# 13_-_ETHERNET_PHY.net
KiCad netlist of a schematic drawn in Altium Designer
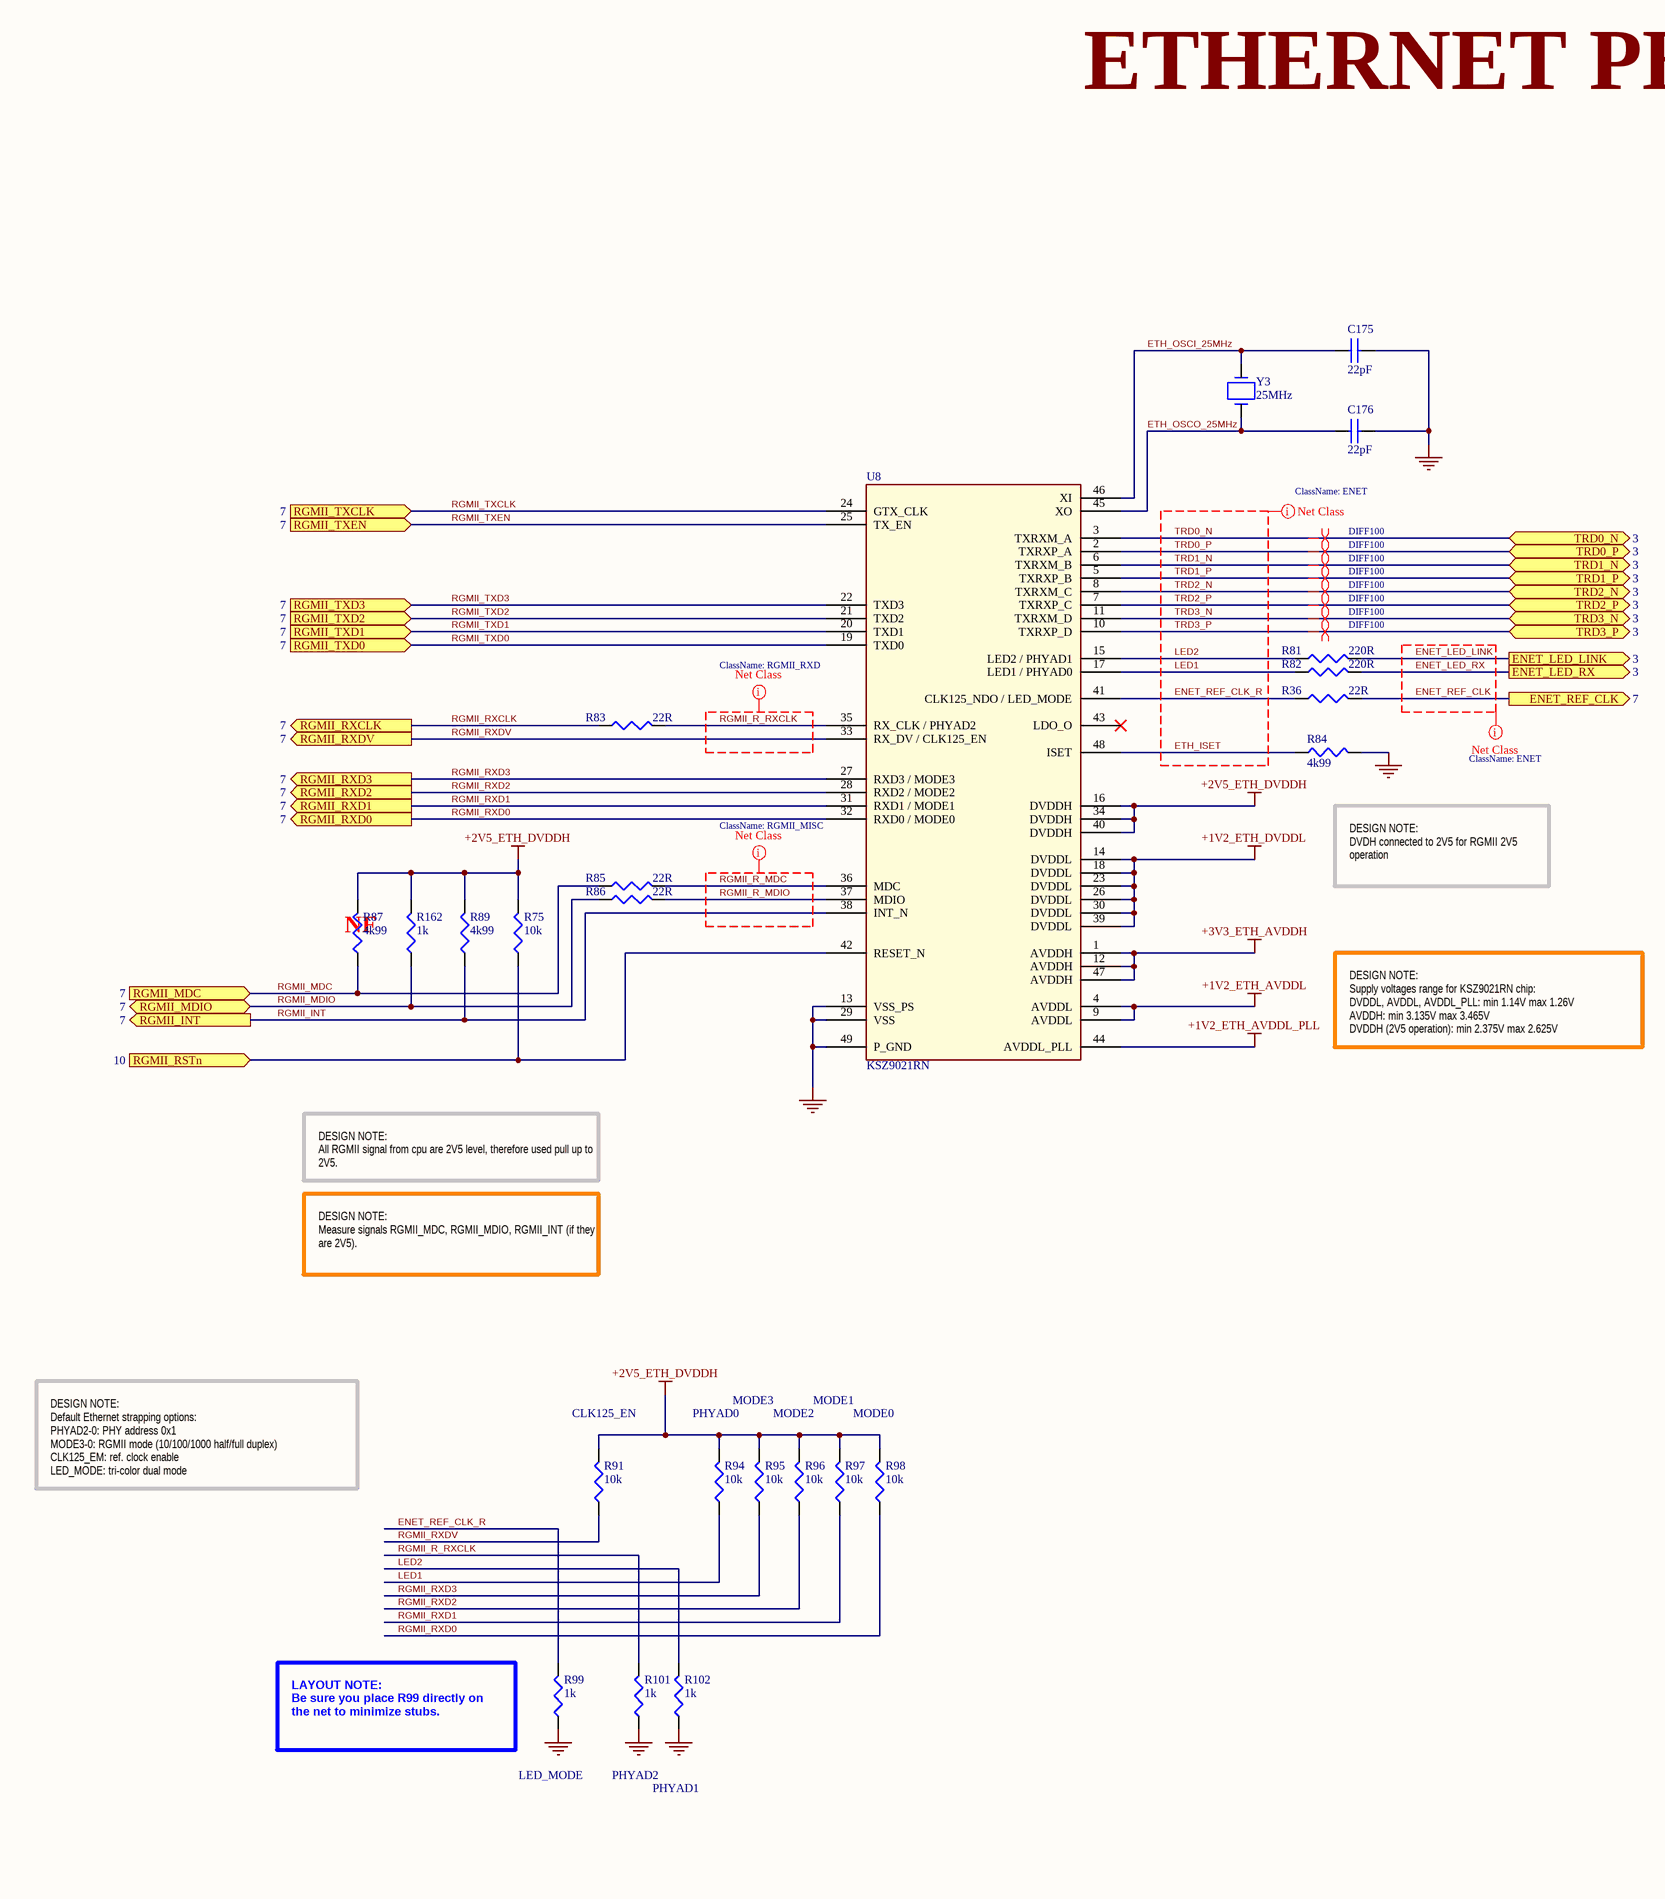
[diagram p0: [13] - ETHERNET PHY.SchDoc, left]
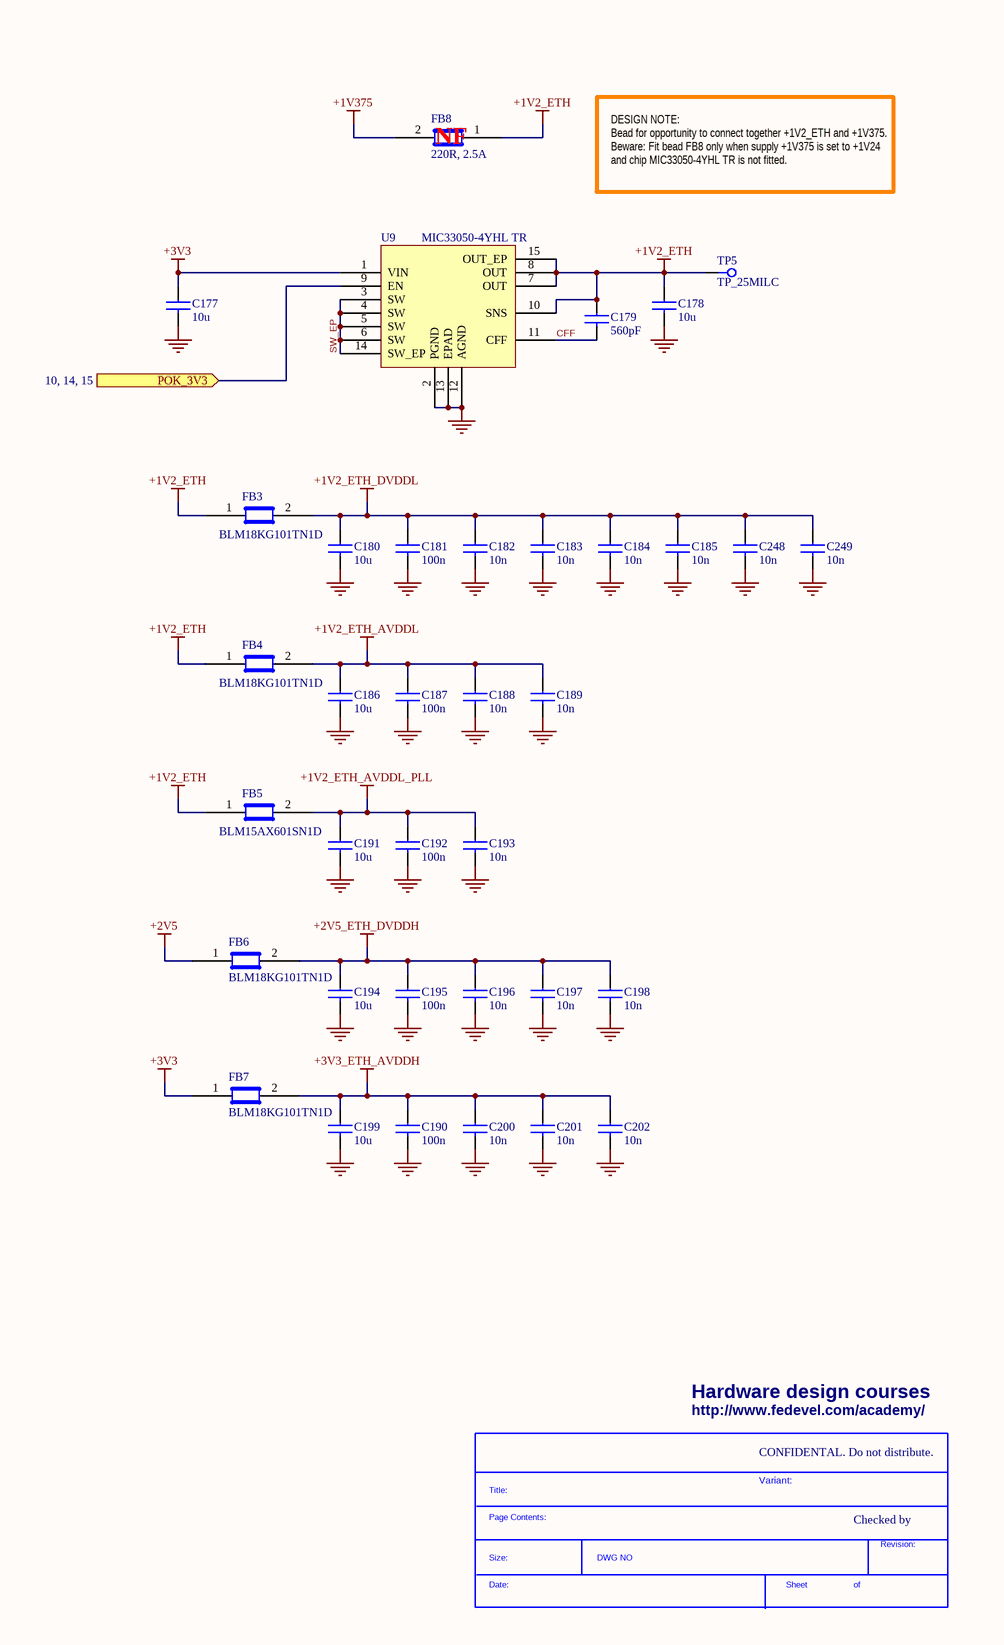
[diagram p1: [13] - ETHERNET PHY.SchDoc, right]

(export (version "E")
  (design (tool "Eeschema 10.0.6"))
  (components
    (comp (ref "C175")
      (value "22pF")
      (footprint "C0402")
      (description "CAP CER 22PF 50V C0G 5% 0402")
      (fields
        (field (name "MANUFACTURER") "TDK Corporation")
        (field (name "MANUFACTURER PART NUMBER") "C1005C0G1H220J")
      )
      (libsource (lib "Integrated_Library_RF_FEB_2012") (part "C1005C0G1H220J"))
    )
    (comp (ref "C176")
      (value "22pF")
      (footprint "C0402")
      (description "CAP CER 22PF 50V C0G 5% 0402")
      (fields
        (field (name "MANUFACTURER") "TDK Corporation")
        (field (name "MANUFACTURER PART NUMBER") "C1005C0G1H220J")
      )
      (libsource (lib "Integrated_Library_RF_FEB_2012") (part "C1005C0G1H220J"))
    )
    (comp (ref "C177")
      (value "10u")
      (footprint "C0603")
      (description "CAP CER 10UF 6.3V X5R 20% 0603")
      (fields
        (field (name "MANUFACTURER") "TDK Corporation")
        (field (name "MANUFACTURER PART NUMBER") "C1608X5R0J106M")
      )
      (libsource (lib "Integrated_Library_RF_FEB_2012") (part "C1608X5R0J106M"))
    )
    (comp (ref "C178")
      (value "10u")
      (footprint "C0603")
      (description "CAP CER 10UF 6.3V X5R 20% 0603")
      (fields
        (field (name "MANUFACTURER") "TDK Corporation")
        (field (name "MANUFACTURER PART NUMBER") "C1608X5R0J106M")
      )
      (libsource (lib "Integrated_Library_RF_FEB_2012") (part "C1608X5R0J106M"))
    )
    (comp (ref "C179")
      (value "560pF")
      (footprint "C0402")
      (description "CAP CER 560PF 50V C0G 0402")
      (fields
        (field (name "MANUFACTURER") "Murata Electronics North America")
        (field (name "MANUFACTURER PART NUMBER") "GRM1555C1H561JA01D")
      )
      (libsource (lib "Integrated_Library_RF_FEB_2012") (part "GRM1555C1H561JA01D"))
    )
    (comp (ref "C180")
      (value "10u")
      (footprint "C0603")
      (description "CAP CER 10UF 6.3V X5R 20% 0603")
      (fields
        (field (name "MANUFACTURER") "TDK Corporation")
        (field (name "MANUFACTURER PART NUMBER") "C1608X5R0J106M")
      )
      (libsource (lib "Integrated_Library_RF_FEB_2012") (part "C1608X5R0J106M"))
    )
    (comp (ref "C181")
      (value "100n")
      (footprint "C0402")
      (description "CAP CER .10UF 50V X5R 10% 0402")
      (fields
        (field (name "MANUFACTURER") "TDK Corporation")
        (field (name "MANUFACTURER PART NUMBER") "C1005X5R1H104K")
      )
      (libsource (lib "Integrated_Library_RF_FEB_2012") (part "C1005X5R1H104K"))
    )
    (comp (ref "C182")
      (value "10n")
      (footprint "C0402")
      (description "CAP CER 10000PF 16V X7R 10% 0402")
      (fields
        (field (name "MANUFACTURER") "TDK Corporation")
        (field (name "MANUFACTURER PART NUMBER") "C1005X7R1C103K")
      )
      (libsource (lib "Integrated_Library_RF_FEB_2012") (part "C1005X7R1C103K"))
    )
    (comp (ref "C183")
      (value "10n")
      (footprint "C0402")
      (description "CAP CER 10000PF 16V X7R 10% 0402")
      (fields
        (field (name "MANUFACTURER") "TDK Corporation")
        (field (name "MANUFACTURER PART NUMBER") "C1005X7R1C103K")
      )
      (libsource (lib "Integrated_Library_RF_FEB_2012") (part "C1005X7R1C103K"))
    )
    (comp (ref "C184")
      (value "10n")
      (footprint "C0402")
      (description "CAP CER 10000PF 16V X7R 10% 0402")
      (fields
        (field (name "MANUFACTURER") "TDK Corporation")
        (field (name "MANUFACTURER PART NUMBER") "C1005X7R1C103K")
      )
      (libsource (lib "Integrated_Library_RF_FEB_2012") (part "C1005X7R1C103K"))
    )
    (comp (ref "C185")
      (value "10n")
      (footprint "C0402")
      (description "CAP CER 10000PF 16V X7R 10% 0402")
      (fields
        (field (name "MANUFACTURER") "TDK Corporation")
        (field (name "MANUFACTURER PART NUMBER") "C1005X7R1C103K")
      )
      (libsource (lib "Integrated_Library_RF_FEB_2012") (part "C1005X7R1C103K"))
    )
    (comp (ref "C186")
      (value "10u")
      (footprint "C0603")
      (description "CAP CER 10UF 6.3V X5R 20% 0603")
      (fields
        (field (name "MANUFACTURER") "TDK Corporation")
        (field (name "MANUFACTURER PART NUMBER") "C1608X5R0J106M")
      )
      (libsource (lib "Integrated_Library_RF_FEB_2012") (part "C1608X5R0J106M"))
    )
    (comp (ref "C187")
      (value "100n")
      (footprint "C0402")
      (description "CAP CER .10UF 50V X5R 10% 0402")
      (fields
        (field (name "MANUFACTURER") "TDK Corporation")
        (field (name "MANUFACTURER PART NUMBER") "C1005X5R1H104K")
      )
      (libsource (lib "Integrated_Library_RF_FEB_2012") (part "C1005X5R1H104K"))
    )
    (comp (ref "C188")
      (value "10n")
      (footprint "C0402")
      (description "CAP CER 10000PF 16V X7R 10% 0402")
      (fields
        (field (name "MANUFACTURER") "TDK Corporation")
        (field (name "MANUFACTURER PART NUMBER") "C1005X7R1C103K")
      )
      (libsource (lib "Integrated_Library_RF_FEB_2012") (part "C1005X7R1C103K"))
    )
    (comp (ref "C189")
      (value "10n")
      (footprint "C0402")
      (description "CAP CER 10000PF 16V X7R 10% 0402")
      (fields
        (field (name "MANUFACTURER") "TDK Corporation")
        (field (name "MANUFACTURER PART NUMBER") "C1005X7R1C103K")
      )
      (libsource (lib "Integrated_Library_RF_FEB_2012") (part "C1005X7R1C103K"))
    )
    (comp (ref "C190")
      (value "100n")
      (footprint "C0402")
      (description "CAP CER .10UF 50V X5R 10% 0402")
      (fields
        (field (name "MANUFACTURER") "TDK Corporation")
        (field (name "MANUFACTURER PART NUMBER") "C1005X5R1H104K")
      )
      (libsource (lib "Integrated_Library_RF_FEB_2012") (part "C1005X5R1H104K"))
    )
    (comp (ref "C191")
      (value "10u")
      (footprint "C0603")
      (description "CAP CER 10UF 6.3V X5R 20% 0603")
      (fields
        (field (name "MANUFACTURER") "TDK Corporation")
        (field (name "MANUFACTURER PART NUMBER") "C1608X5R0J106M")
      )
      (libsource (lib "Integrated_Library_RF_FEB_2012") (part "C1608X5R0J106M"))
    )
    (comp (ref "C192")
      (value "100n")
      (footprint "C0402")
      (description "CAP CER .10UF 50V X5R 10% 0402")
      (fields
        (field (name "MANUFACTURER") "TDK Corporation")
        (field (name "MANUFACTURER PART NUMBER") "C1005X5R1H104K")
      )
      (libsource (lib "Integrated_Library_RF_FEB_2012") (part "C1005X5R1H104K"))
    )
    (comp (ref "C193")
      (value "10n")
      (footprint "C0402")
      (description "CAP CER 10000PF 16V X7R 10% 0402")
      (fields
        (field (name "MANUFACTURER") "TDK Corporation")
        (field (name "MANUFACTURER PART NUMBER") "C1005X7R1C103K")
      )
      (libsource (lib "Integrated_Library_RF_FEB_2012") (part "C1005X7R1C103K"))
    )
    (comp (ref "C194")
      (value "10u")
      (footprint "C0603")
      (description "CAP CER 10UF 6.3V X5R 20% 0603")
      (fields
        (field (name "MANUFACTURER") "TDK Corporation")
        (field (name "MANUFACTURER PART NUMBER") "C1608X5R0J106M")
      )
      (libsource (lib "Integrated_Library_RF_FEB_2012") (part "C1608X5R0J106M"))
    )
    (comp (ref "C195")
      (value "100n")
      (footprint "C0402")
      (description "CAP CER .10UF 50V X5R 10% 0402")
      (fields
        (field (name "MANUFACTURER") "TDK Corporation")
        (field (name "MANUFACTURER PART NUMBER") "C1005X5R1H104K")
      )
      (libsource (lib "Integrated_Library_RF_FEB_2012") (part "C1005X5R1H104K"))
    )
    (comp (ref "C196")
      (value "10n")
      (footprint "C0402")
      (description "CAP CER 10000PF 16V X7R 10% 0402")
      (fields
        (field (name "MANUFACTURER") "TDK Corporation")
        (field (name "MANUFACTURER PART NUMBER") "C1005X7R1C103K")
      )
      (libsource (lib "Integrated_Library_RF_FEB_2012") (part "C1005X7R1C103K"))
    )
    (comp (ref "C197")
      (value "10n")
      (footprint "C0402")
      (description "CAP CER 10000PF 16V X7R 10% 0402")
      (fields
        (field (name "MANUFACTURER") "TDK Corporation")
        (field (name "MANUFACTURER PART NUMBER") "C1005X7R1C103K")
      )
      (libsource (lib "Integrated_Library_RF_FEB_2012") (part "C1005X7R1C103K"))
    )
    (comp (ref "C198")
      (value "10n")
      (footprint "C0402")
      (description "CAP CER 10000PF 16V X7R 10% 0402")
      (fields
        (field (name "MANUFACTURER") "TDK Corporation")
        (field (name "MANUFACTURER PART NUMBER") "C1005X7R1C103K")
      )
      (libsource (lib "Integrated_Library_RF_FEB_2012") (part "C1005X7R1C103K"))
    )
    (comp (ref "C199")
      (value "10u")
      (footprint "C0603")
      (description "CAP CER 10UF 6.3V X5R 20% 0603")
      (fields
        (field (name "MANUFACTURER") "TDK Corporation")
        (field (name "MANUFACTURER PART NUMBER") "C1608X5R0J106M")
      )
      (libsource (lib "Integrated_Library_RF_FEB_2012") (part "C1608X5R0J106M"))
    )
    (comp (ref "C200")
      (value "10n")
      (footprint "C0402")
      (description "CAP CER 10000PF 16V X7R 10% 0402")
      (fields
        (field (name "MANUFACTURER") "TDK Corporation")
        (field (name "MANUFACTURER PART NUMBER") "C1005X7R1C103K")
      )
      (libsource (lib "Integrated_Library_RF_FEB_2012") (part "C1005X7R1C103K"))
    )
    (comp (ref "C201")
      (value "10n")
      (footprint "C0402")
      (description "CAP CER 10000PF 16V X7R 10% 0402")
      (fields
        (field (name "MANUFACTURER") "TDK Corporation")
        (field (name "MANUFACTURER PART NUMBER") "C1005X7R1C103K")
      )
      (libsource (lib "Integrated_Library_RF_FEB_2012") (part "C1005X7R1C103K"))
    )
    (comp (ref "C202")
      (value "10n")
      (footprint "C0402")
      (description "CAP CER 10000PF 16V X7R 10% 0402")
      (fields
        (field (name "MANUFACTURER") "TDK Corporation")
        (field (name "MANUFACTURER PART NUMBER") "C1005X7R1C103K")
      )
      (libsource (lib "Integrated_Library_RF_FEB_2012") (part "C1005X7R1C103K"))
    )
    (comp (ref "C248")
      (value "10n")
      (footprint "C0402")
      (description "CAP CER 10000PF 16V X7R 10% 0402")
      (fields
        (field (name "MANUFACTURER") "TDK Corporation")
        (field (name "MANUFACTURER PART NUMBER") "C1005X7R1C103K")
      )
      (libsource (lib "Integrated_Library_RF_FEB_2012") (part "C1005X7R1C103K"))
    )
    (comp (ref "C249")
      (value "10n")
      (footprint "C0402")
      (description "CAP CER 10000PF 16V X7R 10% 0402")
      (fields
        (field (name "MANUFACTURER") "TDK Corporation")
        (field (name "MANUFACTURER PART NUMBER") "C1005X7R1C103K")
      )
      (libsource (lib "Integrated_Library_RF_FEB_2012") (part "C1005X7R1C103K"))
    )
    (comp (ref "FB3")
      (value "BLM18KG101TN1D")
      (footprint "C0603")
      (description "FERRITE CHIP 100 OHM BEAD 0603")
      (fields (field (name "MANUFACTURER") "Murata Electronics North America"))
      (libsource (lib "Integrated_Library_RF_FEB_2012") (part "BLM18KG101TN1D"))
    )
    (comp (ref "FB4")
      (value "BLM18KG101TN1D")
      (footprint "C0603")
      (description "FERRITE CHIP 100 OHM BEAD 0603")
      (fields (field (name "MANUFACTURER") "Murata Electronics North America"))
      (libsource (lib "Integrated_Library_RF_FEB_2012") (part "BLM18KG101TN1D"))
    )
    (comp (ref "FB5")
      (value "BLM15AX601SN1D")
      (footprint "C0402")
      (description "FERRITE CHIP 600 OHM 0402")
      (fields (field (name "MANUFACTURER") "Murata Electronics North America"))
      (libsource (lib "Integrated_Library_RF_FEB_2012") (part "BLM15AX601SN1D"))
    )
    (comp (ref "FB6")
      (value "BLM18KG101TN1D")
      (footprint "C0603")
      (description "FERRITE CHIP 100 OHM BEAD 0603")
      (fields (field (name "MANUFACTURER") "Murata Electronics North America"))
      (libsource (lib "Integrated_Library_RF_FEB_2012") (part "BLM18KG101TN1D"))
    )
    (comp (ref "FB7")
      (value "BLM18KG101TN1D")
      (footprint "C0603")
      (description "FERRITE CHIP 100 OHM BEAD 0603")
      (fields (field (name "MANUFACTURER") "Murata Electronics North America"))
      (libsource (lib "Integrated_Library_RF_FEB_2012") (part "BLM18KG101TN1D"))
    )
    (comp (ref "FB8")
      (value "220R, 2.5A")
      (footprint "C0603")
      (description "FERRITE CHIP 220 OHM 2500MA 0603")
      (fields
        (field (name "MANUFACTURER") "Murata Electronics North America")
        (field (name "MANUFACTURER PART NUMBER") "BLM18SG221TN1D")
        (field (name ".CHECKED PCB") "RF")
        (field (name ".CHECKED SCH") "RF")
      )
      (libsource (lib "Integrated_Library_RF_FEB_2012") (part "BLM18SG221TN1D"))
    )
    (comp (ref "R36")
      (value "22R")
      (footprint "R0402")
      (description "RES 22.0 OHM 1/16W 1% 0402 SMD")
      (fields
        (field (name "MANUFACTURER") "Yageo")
        (field (name "MANUFACTURER PART NUMBER") "RC0402FR-0722RL")
      )
      (libsource (lib "Integrated_Library_RF_FEB_2012") (part "RC0402FR-0722RL"))
    )
    (comp (ref "R75")
      (value "10k")
      (footprint "R0402")
      (description "RES 10.0K OHM 1/16W 1% 0402 SMD")
      (fields
        (field (name "MANUFACTURER") "Yageo")
        (field (name "MANUFACTURER PART NUMBER") "RC0402FR-0710KL")
      )
      (libsource (lib "Integrated_Library_RF_FEB_2012") (part "RC0402FR-0710KL"))
    )
    (comp (ref "R81")
      (value "220R")
      (footprint "R0402")
      (description "RES 220 OHM 1/16W 1% 0402 SMD")
      (fields
        (field (name "MANUFACTURER") "Yageo")
        (field (name "MANUFACTURER PART NUMBER") "RC0402FR-07220RL")
      )
      (libsource (lib "Integrated_Library_RF_FEB_2012") (part "RC0402FR-07220RL"))
    )
    (comp (ref "R82")
      (value "220R")
      (footprint "R0402")
      (description "RES 220 OHM 1/16W 1% 0402 SMD")
      (fields
        (field (name "MANUFACTURER") "Yageo")
        (field (name "MANUFACTURER PART NUMBER") "RC0402FR-07220RL")
      )
      (libsource (lib "Integrated_Library_RF_FEB_2012") (part "RC0402FR-07220RL"))
    )
    (comp (ref "R83")
      (value "22R")
      (footprint "R0402")
      (description "RES 22.0 OHM 1/16W 1% 0402 SMD")
      (fields
        (field (name "MANUFACTURER") "Yageo")
        (field (name "MANUFACTURER PART NUMBER") "RC0402FR-0722RL")
      )
      (libsource (lib "Integrated_Library_RF_FEB_2012") (part "RC0402FR-0722RL"))
    )
    (comp (ref "R84")
      (value "4k99")
      (footprint "R0402")
      (description "RES TF 4.99K OHM 1% 1/16W 0402")
      (fields
        (field (name "MANUFACTURER") "Stackpole Electronics Inc")
        (field (name "MANUFACTURER PART NUMBER") "RMCF0402FT4K99")
      )
      (libsource (lib "Integrated_Library_RF_FEB_2012") (part "RMCF0402FT4K99"))
    )
    (comp (ref "R85")
      (value "22R")
      (footprint "R0402")
      (description "RES 22.0 OHM 1/16W 1% 0402 SMD")
      (fields
        (field (name "MANUFACTURER") "Yageo")
        (field (name "MANUFACTURER PART NUMBER") "RC0402FR-0722RL")
      )
      (libsource (lib "Integrated_Library_RF_FEB_2012") (part "RC0402FR-0722RL"))
    )
    (comp (ref "R86")
      (value "22R")
      (footprint "R0402")
      (description "RES 22.0 OHM 1/16W 1% 0402 SMD")
      (fields
        (field (name "MANUFACTURER") "Yageo")
        (field (name "MANUFACTURER PART NUMBER") "RC0402FR-0722RL")
      )
      (libsource (lib "Integrated_Library_RF_FEB_2012") (part "RC0402FR-0722RL"))
    )
    (comp (ref "R87")
      (value "4k99")
      (footprint "R0402")
      (description "RES TF 4.99K OHM 1% 1/16W 0402")
      (fields
        (field (name "MANUFACTURER") "Stackpole Electronics Inc")
        (field (name "MANUFACTURER PART NUMBER") "RMCF0402FT4K99")
      )
      (libsource (lib "Integrated_Library_RF_FEB_2012") (part "RMCF0402FT4K99"))
    )
    (comp (ref "R89")
      (value "4k99")
      (footprint "R0402")
      (description "RES TF 4.99K OHM 1% 1/16W 0402")
      (fields
        (field (name "MANUFACTURER") "Stackpole Electronics Inc")
        (field (name "MANUFACTURER PART NUMBER") "RMCF0402FT4K99")
      )
      (libsource (lib "Integrated_Library_RF_FEB_2012") (part "RMCF0402FT4K99"))
    )
    (comp (ref "R91")
      (value "10k")
      (footprint "R0402")
      (description "RES 10.0K OHM 1/16W 1% 0402 SMD")
      (fields
        (field (name "MANUFACTURER") "Yageo")
        (field (name "MANUFACTURER PART NUMBER") "RC0402FR-0710KL")
      )
      (libsource (lib "Integrated_Library_RF_FEB_2012") (part "RC0402FR-0710KL"))
    )
    (comp (ref "R94")
      (value "10k")
      (footprint "R0402")
      (description "RES 10.0K OHM 1/16W 1% 0402 SMD")
      (fields
        (field (name "MANUFACTURER") "Yageo")
        (field (name "MANUFACTURER PART NUMBER") "RC0402FR-0710KL")
      )
      (libsource (lib "Integrated_Library_RF_FEB_2012") (part "RC0402FR-0710KL"))
    )
    (comp (ref "R95")
      (value "10k")
      (footprint "R0402")
      (description "RES 10.0K OHM 1/16W 1% 0402 SMD")
      (fields
        (field (name "MANUFACTURER") "Yageo")
        (field (name "MANUFACTURER PART NUMBER") "RC0402FR-0710KL")
      )
      (libsource (lib "Integrated_Library_RF_FEB_2012") (part "RC0402FR-0710KL"))
    )
    (comp (ref "R96")
      (value "10k")
      (footprint "R0402")
      (description "RES 10.0K OHM 1/16W 1% 0402 SMD")
      (fields
        (field (name "MANUFACTURER") "Yageo")
        (field (name "MANUFACTURER PART NUMBER") "RC0402FR-0710KL")
      )
      (libsource (lib "Integrated_Library_RF_FEB_2012") (part "RC0402FR-0710KL"))
    )
    (comp (ref "R97")
      (value "10k")
      (footprint "R0402")
      (description "RES 10.0K OHM 1/16W 1% 0402 SMD")
      (fields
        (field (name "MANUFACTURER") "Yageo")
        (field (name "MANUFACTURER PART NUMBER") "RC0402FR-0710KL")
      )
      (libsource (lib "Integrated_Library_RF_FEB_2012") (part "RC0402FR-0710KL"))
    )
    (comp (ref "R98")
      (value "10k")
      (footprint "R0402")
      (description "RES 10.0K OHM 1/16W 1% 0402 SMD")
      (fields
        (field (name "MANUFACTURER") "Yageo")
        (field (name "MANUFACTURER PART NUMBER") "RC0402FR-0710KL")
      )
      (libsource (lib "Integrated_Library_RF_FEB_2012") (part "RC0402FR-0710KL"))
    )
    (comp (ref "R99")
      (value "1k")
      (footprint "R0402")
      (description "RES 1.00K OHM 1/16W 1% 0402 SMD")
      (fields
        (field (name "MANUFACTURER") "Yageo")
        (field (name "MANUFACTURER PART NUMBER") "RC0402FR-071KL")
      )
      (libsource (lib "Integrated_Library_RF_FEB_2012") (part "RC0402FR-071KL"))
    )
    (comp (ref "R101")
      (value "1k")
      (footprint "R0402")
      (description "RES 1.00K OHM 1/16W 1% 0402 SMD")
      (fields
        (field (name "MANUFACTURER") "Yageo")
        (field (name "MANUFACTURER PART NUMBER") "RC0402FR-071KL")
      )
      (libsource (lib "Integrated_Library_RF_FEB_2012") (part "RC0402FR-071KL"))
    )
    (comp (ref "R102")
      (value "1k")
      (footprint "R0402")
      (description "RES 1.00K OHM 1/16W 1% 0402 SMD")
      (fields
        (field (name "MANUFACTURER") "Yageo")
        (field (name "MANUFACTURER PART NUMBER") "RC0402FR-071KL")
      )
      (libsource (lib "Integrated_Library_RF_FEB_2012") (part "RC0402FR-071KL"))
    )
    (comp (ref "R162")
      (value "1k")
      (footprint "R0402")
      (description "RES 1.00K OHM 1/16W 1% 0402 SMD")
      (fields
        (field (name "MANUFACTURER") "Yageo")
        (field (name "MANUFACTURER PART NUMBER") "RC0402FR-071KL")
      )
      (libsource (lib "Integrated_Library_RF_FEB_2012") (part "RC0402FR-071KL"))
    )
    (comp (ref "TP5")
      (value "TP_25MILC")
      (footprint "TP_25C")
      (description "Test Point 25mil")
      (libsource (lib "Integrated_Library_RF_FEB_2012") (part "TP_25MILC"))
    )
    (comp (ref "U8")
      (value "KSZ9021RN")
      (footprint "QFN48_7MMX7MM")
      (description "IC TXRX 10/100/1000 SGL 48QFN")
      (fields
        (field (name "MANUFACTURER") "Micrel Inc")
        (field (name ".CREATOR") "MM")
        (field (name ".CHECKED PCB") "MM, checked by RF")
        (field (name ".CHECKED SCH") "MM, checked by RF")
      )
      (libsource (lib "Schlib_RF") (part "KSZ9021RN"))
    )
    (comp (ref "U9")
      (value "MIC33050-4YHL TR")
      (footprint "MLF_3x3_12PINS")
      (description "IC BUCK SYNC 1.2V 0.6A 12MLF")
      (fields (field (name "MANUFACTURER") "Micrel Inc"))
      (libsource (lib "Integrated_Library_RF_FEB_2012") (part "MIC33050-4YHL TR"))
    )
    (comp (ref "Y3")
      (value "25MHz")
      (footprint "ABM7_v1_1")
      (description "CRYSTAL 25.0000 MHZ 18PF SMD")
      (fields
        (field (name "MANUFACTURER") "Abracon Corporation")
        (field (name "MANUFACTURER PART NUMBER") "ABM7-25.000MHZ-D-2-Y-T")
        (field (name ".CHECKED PCB") "RF used by MM")
        (field (name ".CHECKED SCH") "RF used by MM")
      )
      (libsource (lib "Integrated_Library_RF_FEB_2012") (part "ABM7-25.000MHZ-D-2-Y-T V1.1"))
    )
  )
  (nets
    (net (code "1") (name "+1V2_ETH") (class "Default")
      (node (ref "C178") (pin "1") (pinfunction "1_1") (pintype "passive"))
      (node (ref "C179") (pin "1") (pinfunction "1_1") (pintype "passive"))
      (node (ref "FB3") (pin "1") (pinfunction "1_1") (pintype "passive"))
      (node (ref "FB4") (pin "1") (pinfunction "1_1") (pintype "passive"))
      (node (ref "FB5") (pin "1") (pinfunction "1_1") (pintype "passive"))
      (node (ref "FB8") (pin "1") (pinfunction "1_1") (pintype "passive"))
      (node (ref "TP5") (pin "1") (pinfunction "1_1") (pintype "passive"))
      (node (ref "U9") (pin "10") (pinfunction "SNS_10") (pintype "passive"))
      (node (ref "U9") (pin "15") (pinfunction "OUT_EP_15") (pintype "passive"))
      (node (ref "U9") (pin "7") (pinfunction "OUT_7") (pintype "passive"))
      (node (ref "U9") (pin "8") (pinfunction "OUT_8") (pintype "passive"))
    )
    (net (code "2") (name "+1V2_ETH_AVDDL") (class "Default")
      (node (ref "C186") (pin "1") (pinfunction "1_1") (pintype "passive"))
      (node (ref "C187") (pin "1") (pinfunction "1_1") (pintype "passive"))
      (node (ref "C188") (pin "1") (pinfunction "1_1") (pintype "passive"))
      (node (ref "C189") (pin "1") (pinfunction "1_1") (pintype "passive"))
      (node (ref "FB4") (pin "2") (pinfunction "2_2") (pintype "passive"))
      (node (ref "U8") (pin "4") (pinfunction "AVDDL_4") (pintype "passive"))
      (node (ref "U8") (pin "9") (pinfunction "AVDDL_9") (pintype "passive"))
    )
    (net (code "3") (name "+1V2_ETH_AVDDL_PLL") (class "Default")
      (node (ref "C191") (pin "1") (pinfunction "1_1") (pintype "passive"))
      (node (ref "C192") (pin "1") (pinfunction "1_1") (pintype "passive"))
      (node (ref "C193") (pin "1") (pinfunction "1_1") (pintype "passive"))
      (node (ref "FB5") (pin "2") (pinfunction "2_2") (pintype "passive"))
      (node (ref "U8") (pin "44") (pinfunction "AVDDL_PLL_44") (pintype "passive"))
    )
    (net (code "4") (name "+1V2_ETH_DVDDL") (class "Default")
      (node (ref "C180") (pin "1") (pinfunction "1_1") (pintype "passive"))
      (node (ref "C181") (pin "1") (pinfunction "1_1") (pintype "passive"))
      (node (ref "C182") (pin "1") (pinfunction "1_1") (pintype "passive"))
      (node (ref "C183") (pin "1") (pinfunction "1_1") (pintype "passive"))
      (node (ref "C184") (pin "1") (pinfunction "1_1") (pintype "passive"))
      (node (ref "C185") (pin "1") (pinfunction "1_1") (pintype "passive"))
      (node (ref "C248") (pin "1") (pinfunction "1_1") (pintype "passive"))
      (node (ref "C249") (pin "1") (pinfunction "1_1") (pintype "passive"))
      (node (ref "FB3") (pin "2") (pinfunction "2_2") (pintype "passive"))
      (node (ref "U8") (pin "14") (pinfunction "DVDDL_14") (pintype "passive"))
      (node (ref "U8") (pin "18") (pinfunction "DVDDL_18") (pintype "passive"))
      (node (ref "U8") (pin "23") (pinfunction "DVDDL_23") (pintype "passive"))
      (node (ref "U8") (pin "26") (pinfunction "DVDDL_26") (pintype "passive"))
      (node (ref "U8") (pin "30") (pinfunction "DVDDL_30") (pintype "passive"))
      (node (ref "U8") (pin "39") (pinfunction "DVDDL_39") (pintype "passive"))
    )
    (net (code "5") (name "+1V375") (class "Default")
      (node (ref "FB8") (pin "2") (pinfunction "2_2") (pintype "passive"))
    )
    (net (code "6") (name "+2V5") (class "Default")
      (node (ref "FB6") (pin "1") (pinfunction "1_1") (pintype "passive"))
    )
    (net (code "7") (name "+2V5_ETH_DVDDH") (class "Default")
      (node (ref "C194") (pin "1") (pinfunction "1_1") (pintype "passive"))
      (node (ref "C195") (pin "1") (pinfunction "1_1") (pintype "passive"))
      (node (ref "C196") (pin "1") (pinfunction "1_1") (pintype "passive"))
      (node (ref "C197") (pin "1") (pinfunction "1_1") (pintype "passive"))
      (node (ref "C198") (pin "1") (pinfunction "1_1") (pintype "passive"))
      (node (ref "FB6") (pin "2") (pinfunction "2_2") (pintype "passive"))
      (node (ref "R162") (pin "2") (pinfunction "2_2") (pintype "passive"))
      (node (ref "R75") (pin "2") (pinfunction "2_2") (pintype "passive"))
      (node (ref "R87") (pin "2") (pinfunction "2_2") (pintype "passive"))
      (node (ref "R89") (pin "2") (pinfunction "2_2") (pintype "passive"))
      (node (ref "R91") (pin "2") (pinfunction "2_2") (pintype "passive"))
      (node (ref "R94") (pin "2") (pinfunction "2_2") (pintype "passive"))
      (node (ref "R95") (pin "2") (pinfunction "2_2") (pintype "passive"))
      (node (ref "R96") (pin "2") (pinfunction "2_2") (pintype "passive"))
      (node (ref "R97") (pin "2") (pinfunction "2_2") (pintype "passive"))
      (node (ref "R98") (pin "2") (pinfunction "2_2") (pintype "passive"))
      (node (ref "U8") (pin "16") (pinfunction "DVDDH_16") (pintype "passive"))
      (node (ref "U8") (pin "34") (pinfunction "DVDDH_34") (pintype "passive"))
      (node (ref "U8") (pin "40") (pinfunction "DVDDH_40") (pintype "passive"))
    )
    (net (code "8") (name "+3V3") (class "Default")
      (node (ref "C177") (pin "1") (pinfunction "1_1") (pintype "passive"))
      (node (ref "FB7") (pin "1") (pinfunction "1_1") (pintype "passive"))
      (node (ref "U9") (pin "1") (pinfunction "VIN_1") (pintype "passive"))
    )
    (net (code "9") (name "+3V3_ETH_AVDDH") (class "Default")
      (node (ref "C190") (pin "1") (pinfunction "1_1") (pintype "passive"))
      (node (ref "C199") (pin "1") (pinfunction "1_1") (pintype "passive"))
      (node (ref "C200") (pin "1") (pinfunction "1_1") (pintype "passive"))
      (node (ref "C201") (pin "1") (pinfunction "1_1") (pintype "passive"))
      (node (ref "C202") (pin "1") (pinfunction "1_1") (pintype "passive"))
      (node (ref "FB7") (pin "2") (pinfunction "2_2") (pintype "passive"))
      (node (ref "U8") (pin "1") (pinfunction "AVDDH_1") (pintype "passive"))
      (node (ref "U8") (pin "12") (pinfunction "AVDDH_12") (pintype "passive"))
      (node (ref "U8") (pin "47") (pinfunction "AVDDH_47") (pintype "passive"))
    )
    (net (code "10") (name "/CFF") (class "Default")
      (node (ref "C179") (pin "2") (pinfunction "2_2") (pintype "passive"))
      (node (ref "U9") (pin "11") (pinfunction "CFF_11") (pintype "passive"))
    )
    (net (code "11") (name "/ENET_LED_LINK") (class "Default")
      (node (ref "R81") (pin "2") (pinfunction "2_2") (pintype "passive"))
    )
    (net (code "12") (name "/ENET_LED_RX") (class "Default")
      (node (ref "R82") (pin "2") (pinfunction "2_2") (pintype "passive"))
    )
    (net (code "13") (name "/ENET_REF_CLK") (class "Default")
      (node (ref "R36") (pin "2") (pinfunction "2_2") (pintype "passive"))
    )
    (net (code "14") (name "/ENET_REF_CLK_R") (class "Default")
      (node (ref "R36") (pin "1") (pinfunction "1_1") (pintype "passive"))
      (node (ref "R99") (pin "2") (pinfunction "2_2") (pintype "passive"))
      (node (ref "U8") (pin "41") (pinfunction "CLK125_NDO_/_LED_MODE_41") (pintype "passive"))
    )
    (net (code "15") (name "/ETH_ISET") (class "Default")
      (node (ref "R84") (pin "1") (pinfunction "1_1") (pintype "passive"))
      (node (ref "U8") (pin "48") (pinfunction "ISET_48") (pintype "passive"))
    )
    (net (code "16") (name "/ETH_OSCI_25MHz") (class "Default")
      (node (ref "C175") (pin "1") (pinfunction "1_1") (pintype "passive"))
      (node (ref "U8") (pin "46") (pinfunction "XI_46") (pintype "passive"))
      (node (ref "Y3") (pin "2") (pinfunction "2_2") (pintype "passive"))
    )
    (net (code "17") (name "/ETH_OSCO_25MHz") (class "Default")
      (node (ref "C176") (pin "1") (pinfunction "1_1") (pintype "passive"))
      (node (ref "U8") (pin "45") (pinfunction "XO_45") (pintype "passive"))
      (node (ref "Y3") (pin "1") (pinfunction "1_1") (pintype "passive"))
    )
    (net (code "18") (name "/LED1") (class "Default")
      (node (ref "R82") (pin "1") (pinfunction "1_1") (pintype "passive"))
      (node (ref "R94") (pin "1") (pinfunction "1_1") (pintype "passive"))
      (node (ref "U8") (pin "17") (pinfunction "LED1_/_PHYAD0_17") (pintype "passive"))
    )
    (net (code "19") (name "/LED2") (class "Default")
      (node (ref "R102") (pin "2") (pinfunction "2_2") (pintype "passive"))
      (node (ref "R81") (pin "1") (pinfunction "1_1") (pintype "passive"))
      (node (ref "U8") (pin "15") (pinfunction "LED2_/_PHYAD1_15") (pintype "passive"))
    )
    (net (code "20") (name "/POK_3V3") (class "Default")
      (node (ref "U9") (pin "9") (pinfunction "EN_9") (pintype "passive"))
    )
    (net (code "21") (name "/RGMII_INT") (class "Default")
      (node (ref "R89") (pin "1") (pinfunction "1_1") (pintype "passive"))
      (node (ref "U8") (pin "38") (pinfunction "INT_N_38") (pintype "passive"))
    )
    (net (code "22") (name "/RGMII_MDC") (class "Default")
      (node (ref "R85") (pin "1") (pinfunction "1_1") (pintype "passive"))
      (node (ref "R87") (pin "1") (pinfunction "1_1") (pintype "passive"))
    )
    (net (code "23") (name "/RGMII_MDIO") (class "Default")
      (node (ref "R162") (pin "1") (pinfunction "1_1") (pintype "passive"))
      (node (ref "R86") (pin "1") (pinfunction "1_1") (pintype "passive"))
    )
    (net (code "24") (name "/RGMII_RSTn") (class "Default")
      (node (ref "R75") (pin "1") (pinfunction "1_1") (pintype "passive"))
      (node (ref "U8") (pin "42") (pinfunction "RESET_N_42") (pintype "passive"))
    )
    (net (code "25") (name "/RGMII_RXCLK") (class "Default")
      (node (ref "R83") (pin "1") (pinfunction "1_1") (pintype "passive"))
    )
    (net (code "26") (name "/RGMII_RXD0") (class "Default")
      (node (ref "R98") (pin "1") (pinfunction "1_1") (pintype "passive"))
      (node (ref "U8") (pin "32") (pinfunction "RXD0_/_MODE0_32") (pintype "passive"))
    )
    (net (code "27") (name "/RGMII_RXD1") (class "Default")
      (node (ref "R97") (pin "1") (pinfunction "1_1") (pintype "passive"))
      (node (ref "U8") (pin "31") (pinfunction "RXD1_/_MODE1_31") (pintype "passive"))
    )
    (net (code "28") (name "/RGMII_RXD2") (class "Default")
      (node (ref "R96") (pin "1") (pinfunction "1_1") (pintype "passive"))
      (node (ref "U8") (pin "28") (pinfunction "RXD2_/_MODE2_28") (pintype "passive"))
    )
    (net (code "29") (name "/RGMII_RXD3") (class "Default")
      (node (ref "R95") (pin "1") (pinfunction "1_1") (pintype "passive"))
      (node (ref "U8") (pin "27") (pinfunction "RXD3_/_MODE3_27") (pintype "passive"))
    )
    (net (code "30") (name "/RGMII_RXDV") (class "Default")
      (node (ref "R91") (pin "1") (pinfunction "1_1") (pintype "passive"))
      (node (ref "U8") (pin "33") (pinfunction "RX_DV_/_CLK125_EN_33") (pintype "passive"))
    )
    (net (code "31") (name "/RGMII_R_MDC") (class "Default")
      (node (ref "R85") (pin "2") (pinfunction "2_2") (pintype "passive"))
      (node (ref "U8") (pin "36") (pinfunction "MDC_36") (pintype "passive"))
    )
    (net (code "32") (name "/RGMII_R_MDIO") (class "Default")
      (node (ref "R86") (pin "2") (pinfunction "2_2") (pintype "passive"))
      (node (ref "U8") (pin "37") (pinfunction "MDIO_37") (pintype "passive"))
    )
    (net (code "33") (name "/RGMII_R_RXCLK") (class "Default")
      (node (ref "R101") (pin "2") (pinfunction "2_2") (pintype "passive"))
      (node (ref "R83") (pin "2") (pinfunction "2_2") (pintype "passive"))
      (node (ref "U8") (pin "35") (pinfunction "RX_CLK_/_PHYAD2_35") (pintype "passive"))
    )
    (net (code "34") (name "/RGMII_TXCLK") (class "Default")
      (node (ref "U8") (pin "24") (pinfunction "GTX_CLK_24") (pintype "passive"))
    )
    (net (code "35") (name "/RGMII_TXD0") (class "Default")
      (node (ref "U8") (pin "19") (pinfunction "TXD0_19") (pintype "passive"))
    )
    (net (code "36") (name "/RGMII_TXD1") (class "Default")
      (node (ref "U8") (pin "20") (pinfunction "TXD1_20") (pintype "passive"))
    )
    (net (code "37") (name "/RGMII_TXD2") (class "Default")
      (node (ref "U8") (pin "21") (pinfunction "TXD2_21") (pintype "passive"))
    )
    (net (code "38") (name "/RGMII_TXD3") (class "Default")
      (node (ref "U8") (pin "22") (pinfunction "TXD3_22") (pintype "passive"))
    )
    (net (code "39") (name "/RGMII_TXEN") (class "Default")
      (node (ref "U8") (pin "25") (pinfunction "TX_EN_25") (pintype "passive"))
    )
    (net (code "40") (name "/SW_EP") (class "Default")
      (node (ref "U9") (pin "14") (pinfunction "SW_EP_14") (pintype "passive"))
      (node (ref "U9") (pin "3") (pinfunction "SW_3") (pintype "passive"))
      (node (ref "U9") (pin "4") (pinfunction "SW_4") (pintype "passive"))
      (node (ref "U9") (pin "5") (pinfunction "SW_5") (pintype "passive"))
      (node (ref "U9") (pin "6") (pinfunction "SW_6") (pintype "passive"))
    )
    (net (code "41") (name "/TRD0_N") (class "Default")
      (node (ref "U8") (pin "3") (pinfunction "TXRXM_A_3") (pintype "passive"))
    )
    (net (code "42") (name "/TRD0_P") (class "Default")
      (node (ref "U8") (pin "2") (pinfunction "TXRXP_A_2") (pintype "passive"))
    )
    (net (code "43") (name "/TRD1_N") (class "Default")
      (node (ref "U8") (pin "6") (pinfunction "TXRXM_B_6") (pintype "passive"))
    )
    (net (code "44") (name "/TRD1_P") (class "Default")
      (node (ref "U8") (pin "5") (pinfunction "TXRXP_B_5") (pintype "passive"))
    )
    (net (code "45") (name "/TRD2_N") (class "Default")
      (node (ref "U8") (pin "8") (pinfunction "TXRXM_C_8") (pintype "passive"))
    )
    (net (code "46") (name "/TRD2_P") (class "Default")
      (node (ref "U8") (pin "7") (pinfunction "TXRXP_C_7") (pintype "passive"))
    )
    (net (code "47") (name "/TRD3_N") (class "Default")
      (node (ref "U8") (pin "11") (pinfunction "TXRXM_D_11") (pintype "passive"))
    )
    (net (code "48") (name "/TRD3_P") (class "Default")
      (node (ref "U8") (pin "10") (pinfunction "TXRXP_D_10") (pintype "passive"))
    )
    (net (code "49") (name "GND") (class "Default")
      (node (ref "C175") (pin "2") (pinfunction "2_2") (pintype "passive"))
      (node (ref "C176") (pin "2") (pinfunction "2_2") (pintype "passive"))
      (node (ref "C177") (pin "2") (pinfunction "2_2") (pintype "passive"))
      (node (ref "C178") (pin "2") (pinfunction "2_2") (pintype "passive"))
      (node (ref "C180") (pin "2") (pinfunction "2_2") (pintype "passive"))
      (node (ref "C181") (pin "2") (pinfunction "2_2") (pintype "passive"))
      (node (ref "C182") (pin "2") (pinfunction "2_2") (pintype "passive"))
      (node (ref "C183") (pin "2") (pinfunction "2_2") (pintype "passive"))
      (node (ref "C184") (pin "2") (pinfunction "2_2") (pintype "passive"))
      (node (ref "C185") (pin "2") (pinfunction "2_2") (pintype "passive"))
      (node (ref "C186") (pin "2") (pinfunction "2_2") (pintype "passive"))
      (node (ref "C187") (pin "2") (pinfunction "2_2") (pintype "passive"))
      (node (ref "C188") (pin "2") (pinfunction "2_2") (pintype "passive"))
      (node (ref "C189") (pin "2") (pinfunction "2_2") (pintype "passive"))
      (node (ref "C190") (pin "2") (pinfunction "2_2") (pintype "passive"))
      (node (ref "C191") (pin "2") (pinfunction "2_2") (pintype "passive"))
      (node (ref "C192") (pin "2") (pinfunction "2_2") (pintype "passive"))
      (node (ref "C193") (pin "2") (pinfunction "2_2") (pintype "passive"))
      (node (ref "C194") (pin "2") (pinfunction "2_2") (pintype "passive"))
      (node (ref "C195") (pin "2") (pinfunction "2_2") (pintype "passive"))
      (node (ref "C196") (pin "2") (pinfunction "2_2") (pintype "passive"))
      (node (ref "C197") (pin "2") (pinfunction "2_2") (pintype "passive"))
      (node (ref "C198") (pin "2") (pinfunction "2_2") (pintype "passive"))
      (node (ref "C199") (pin "2") (pinfunction "2_2") (pintype "passive"))
      (node (ref "C200") (pin "2") (pinfunction "2_2") (pintype "passive"))
      (node (ref "C201") (pin "2") (pinfunction "2_2") (pintype "passive"))
      (node (ref "C202") (pin "2") (pinfunction "2_2") (pintype "passive"))
      (node (ref "C248") (pin "2") (pinfunction "2_2") (pintype "passive"))
      (node (ref "C249") (pin "2") (pinfunction "2_2") (pintype "passive"))
      (node (ref "R101") (pin "1") (pinfunction "1_1") (pintype "passive"))
      (node (ref "R102") (pin "1") (pinfunction "1_1") (pintype "passive"))
      (node (ref "R84") (pin "2") (pinfunction "2_2") (pintype "passive"))
      (node (ref "R99") (pin "1") (pinfunction "1_1") (pintype "passive"))
      (node (ref "U8") (pin "13") (pinfunction "VSS_PS_13") (pintype "passive"))
      (node (ref "U8") (pin "29") (pinfunction "VSS_29") (pintype "passive"))
      (node (ref "U8") (pin "49") (pinfunction "P_GND_49") (pintype "passive"))
      (node (ref "U9") (pin "12") (pinfunction "AGND_12") (pintype "passive"))
      (node (ref "U9") (pin "13") (pinfunction "EPAD_13") (pintype "passive"))
      (node (ref "U9") (pin "2") (pinfunction "PGND_2") (pintype "passive"))
    )
    (net (code "50") (name "unconnected-(U8-LDO_O-Pad43)") (class "Default")
      (node (ref "U8") (pin "43") (pinfunction "LDO_O_43") (pintype "passive+no_connect"))
    )
  )
)
